# CAN_ESP_control.net
KiCad netlist of a schematic drawn in Altium Designer
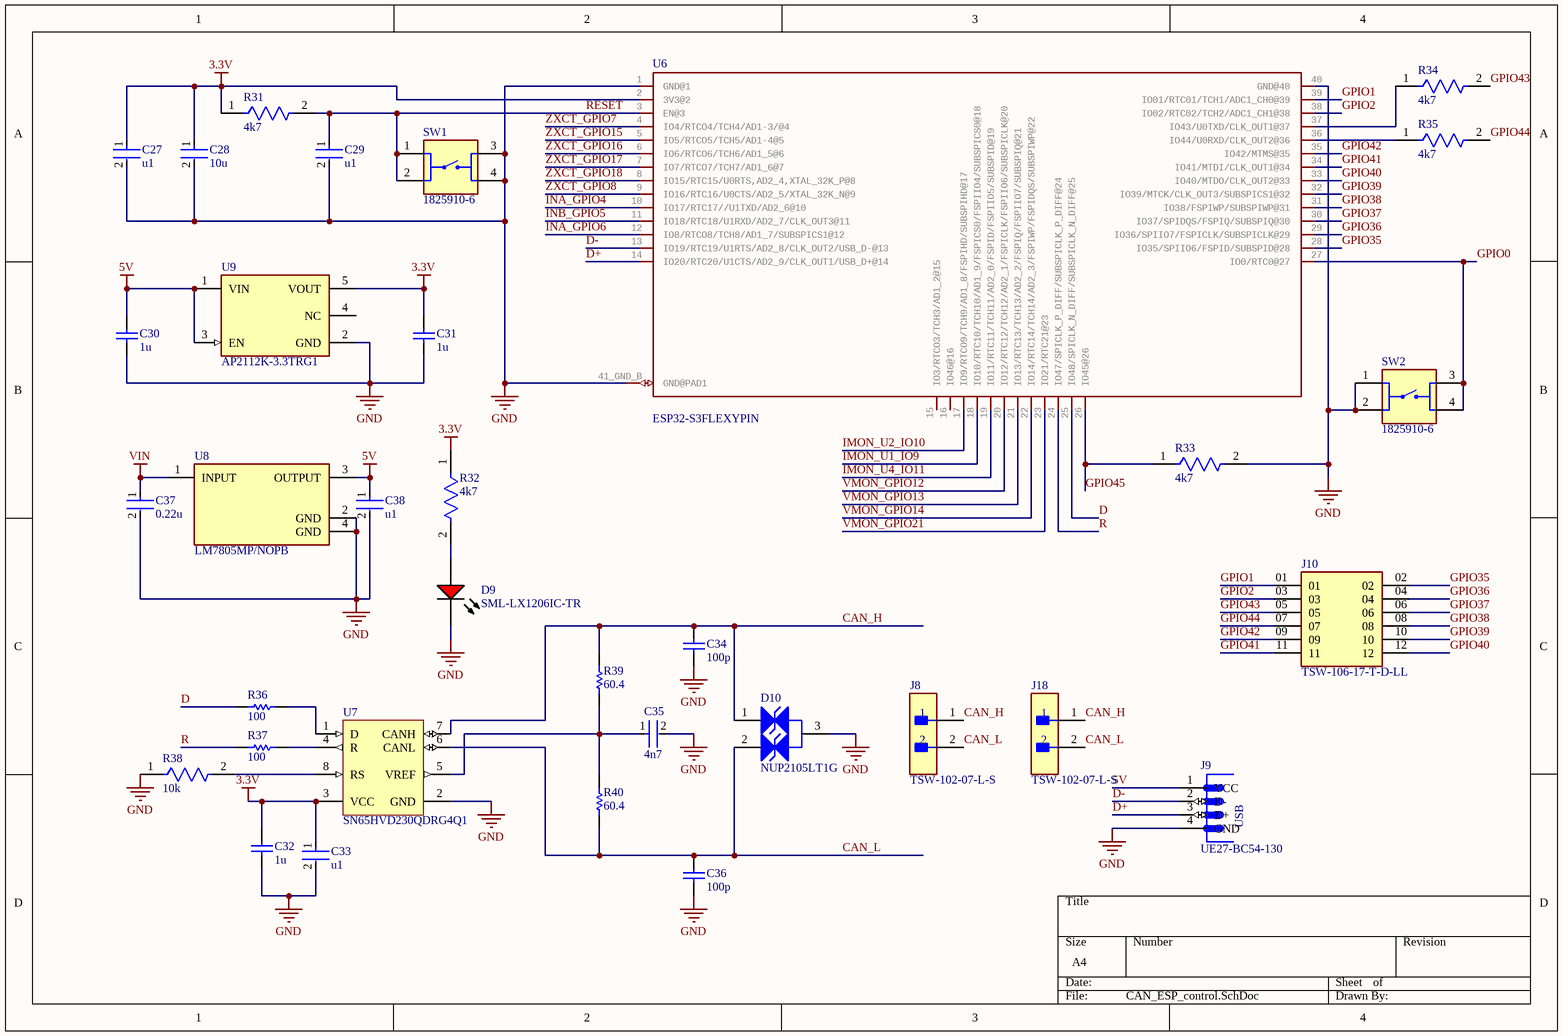
[diagram p0: CAN_ESP_control.SchDoc]

(export (version "E")
  (design (tool "Eeschema 10.0.6"))
  (components
    (comp (ref "C27")
      (value "u1")
      (footprint "FP-CC0805-0_85-MFG")
      (description "CC0805KRX7R9BB104 CAP CER 0.1UF 50V X7R 0805")
      (fields (field (name "TOLERANCE") "0.1") (field (name "MANUFACTURER PART NUMBER") "CC0805KRX7R9BB104"))
      (libsource (lib "Altium Content Vault") (part "11868f565c42a9108669ba33697ecf6"))
    )
    (comp (ref "C28")
      (value "10u")
      (footprint "FP-C0805C-DG-MFG")
      (description "CAP CER 10UF 10V X5R 0805")
      (fields (field (name "TOLERANCE") "10%") (field (name "MANUFACTURER PART NUMBER") "C0805C106K8PACTU"))
      (libsource (lib "Altium Content Vault") (part "11868f565c42a9108669ba33697ecf6"))
    )
    (comp (ref "C29")
      (value "u1")
      (footprint "FP-CC0805-0_85-MFG")
      (description "CC0805KRX7R9BB104 CAP CER 0.1UF 50V X7R 0805")
      (fields (field (name "TOLERANCE") "0.1") (field (name "MANUFACTURER PART NUMBER") "CC0805KRX7R9BB104"))
      (libsource (lib "Altium Content Vault") (part "11868f565c42a9108669ba33697ecf6"))
    )
    (comp (ref "C30")
      (value "1u")
      (footprint "CAPC2013X140X50ML20T25")
      (fields (field (name "MANUFACTURER") "Kemet") (field (name "PART NUMBER") "C0805C105K5RACTU"))
      (libsource (lib "Altium Content Vault") (part "CAP"))
    )
    (comp (ref "C31")
      (value "1u")
      (footprint "CAPC2013X140X50ML20T25")
      (fields (field (name "MANUFACTURER") "Kemet") (field (name "PART NUMBER") "C0805C105K5RACTU"))
      (libsource (lib "Altium Content Vault") (part "CAP"))
    )
    (comp (ref "C32")
      (value "1u")
      (footprint "CAPC2013X140X50ML20T25")
      (fields (field (name "MANUFACTURER") "Kemet") (field (name "PART NUMBER") "C0805C105K5RACTU"))
      (libsource (lib "Altium Content Vault") (part "CAP"))
    )
    (comp (ref "C33")
      (value "u1")
      (footprint "FP-CC0805-0_85-MFG")
      (description "CC0805KRX7R9BB104 CAP CER 0.1UF 50V X7R 0805")
      (fields (field (name "TOLERANCE") "0.1") (field (name "MANUFACTURER PART NUMBER") "CC0805KRX7R9BB104"))
      (libsource (lib "Altium Content Vault") (part "11868f565c42a9108669ba33697ecf6"))
    )
    (comp (ref "C34")
      (value "100p")
      (footprint "CAPC2013X88X50ML20T25")
      (description "C0805C101JCGACTU")
      (fields (field (name "MANUFACTURER") "Kemet"))
      (libsource (lib "Altium Content Vault") (part "CAP"))
    )
    (comp (ref "C35")
      (value "4n7")
      (footprint "FP-0805-L_2_01_0_2-W_1_25-IPC_B")
      (description "08055C472KAT2A General Purpose Ceramic Capacitor, 0805, 4.7nF, 10%, X7R, 0.15, 50V")
      (fields (field (name "VOLTAGE") "50V") (field (name "TOLERANCE") "10%"))
      (libsource (lib "Altium Content Vault") (part "02cd4be3c70576c341d710602a673aa"))
    )
    (comp (ref "C36")
      (value "100p")
      (footprint "CAPC2013X88X50ML20T25")
      (description "C0805C101JCGACTU")
      (fields (field (name "MANUFACTURER") "Kemet"))
      (libsource (lib "Altium Content Vault") (part "CAP"))
    )
    (comp (ref "C37")
      (value "0.22u")
      (footprint "FP-C0805C-DN-MFG")
      (description "CAP CER 0.22UF 50V X7R 0805")
      (fields
        (field (name "MANUFACTURER") "KEMET")
        (field (name "OCTOPART") "https://octopart.com/c0805c224k5ractu-kemet-144670")
      )
      (libsource (lib "Altium Content Vault") (part "b4654b650e69147ec39a6b967a45e02"))
    )
    (comp (ref "C38")
      (value "u1")
      (footprint "FP-CC0805-0_85-MFG")
      (description "CC0805KRX7R9BB104 CAP CER 0.1UF 50V X7R 0805")
      (fields (field (name "TOLERANCE") "0.1") (field (name "MANUFACTURER PART NUMBER") "CC0805KRX7R9BB104"))
      (libsource (lib "Altium Content Vault") (part "11868f565c42a9108669ba33697ecf6"))
    )
    (comp (ref "D9")
      (value "SML-LX1206IC-TR")
      (footprint "LUMX-SML-LX1206IC_V")
      (description "LED Red, 65 mW, -40 to 85 degC, 2-Pin SMD, RoHS, Tape and Reel")
      (fields (field (name "MANUFACTURER") "Lumex"))
      (libsource (lib "Altium Content Vault") (part "LED-RED-AK-2"))
    )
    (comp (ref "D10")
      (value "NUP2105LT1G")
      (footprint "ONSC-SOT-23-3-318-08_V")
      (description "Dual Line CAN Bus Protector, 3-Pin SOT-23, Pb-Free, Tape and Reel")
      (fields (field (name "MANUFACTURER") "On Semiconductor"))
      (libsource (lib "Altium Content Vault") (part "ONSC-NUP21X5X-SOT-23-3-318-08"))
    )
    (comp (ref "J8")
      (value "TSW-102-07-L-S")
      (footprint "FP-TSW-102-07-L-S-MFG")
      (description "CONN HEADER VERT 2POS 2.54MM")
      (libsource (lib "Altium Content Vault") (part "3bc925449376181038e59eaffc5286c"))
    )
    (comp (ref "J9")
      (value "UE27-BC54-130")
      (footprint "AMPHENOL_UE27-BC54-130")
      (description "connector, universal serial bus, type b, rt angle receptacle, black, 4 contact")
      (libsource (lib "PowerDistribution") (part "UE27-BC54-130"))
    )
    (comp (ref "J10")
      (value "TSW-106-17-T-D-LL")
      (footprint "SAMTEC_TSW-106-17-T-D-LL")
      (libsource (lib "PowerDistribution") (part "TSW-106-17-T-D-LL"))
    )
    (comp (ref "J18")
      (value "TSW-102-07-L-S")
      (footprint "FP-TSW-102-07-L-S-MFG")
      (description "CONN HEADER VERT 2POS 2.54MM")
      (libsource (lib "Altium Content Vault") (part "3bc925449376181038e59eaffc5286c"))
    )
    (comp (ref "R31")
      (value "4k7")
      (footprint "FP-CRCW0805-e3-IPC_B")
      (description "CRCW08054K70FKEARES Thick Film, 4.7kΩ, 1%, 0.125W, 100ppm/°C, 0805")
      (fields (field (name "TOLERANCE") "1%"))
      (libsource (lib "Altium Content Vault") (part "1029c3af85768c4190bb7ad29bc67b5"))
    )
    (comp (ref "R32")
      (value "4k7")
      (footprint "FP-CRCW0805-e3-IPC_B")
      (description "CRCW08054K70FKEARES Thick Film, 4.7kΩ, 1%, 0.125W, 100ppm/°C, 0805")
      (fields (field (name "TOLERANCE") "1%"))
      (libsource (lib "Altium Content Vault") (part "1029c3af85768c4190bb7ad29bc67b5"))
    )
    (comp (ref "R33")
      (value "4k7")
      (footprint "FP-CRCW0805-e3-IPC_B")
      (description "CRCW08054K70FKEARES Thick Film, 4.7kΩ, 1%, 0.125W, 100ppm/°C, 0805")
      (fields (field (name "TOLERANCE") "1%"))
      (libsource (lib "Altium Content Vault") (part "1029c3af85768c4190bb7ad29bc67b5"))
    )
    (comp (ref "R34")
      (value "4k7")
      (footprint "FP-CRCW0805-e3-IPC_B")
      (description "CRCW08054K70FKEARES Thick Film, 4.7kΩ, 1%, 0.125W, 100ppm/°C, 0805")
      (fields (field (name "TOLERANCE") "1%"))
      (libsource (lib "Altium Content Vault") (part "1029c3af85768c4190bb7ad29bc67b5"))
    )
    (comp (ref "R35")
      (value "4k7")
      (footprint "FP-CRCW0805-e3-IPC_B")
      (description "CRCW08054K70FKEARES Thick Film, 4.7kΩ, 1%, 0.125W, 100ppm/°C, 0805")
      (fields (field (name "TOLERANCE") "1%"))
      (libsource (lib "Altium Content Vault") (part "1029c3af85768c4190bb7ad29bc67b5"))
    )
    (comp (ref "R36")
      (value "100")
      (footprint "RESC2013X60X35ML10T20")
      (fields (field (name "TOLERANCE") "1%") (field (name "MANUFACTURER") "Yageo"))
      (libsource (lib "Altium Content Vault") (part "RES-2"))
    )
    (comp (ref "R37")
      (value "100")
      (footprint "RESC2013X60X35ML10T20")
      (fields (field (name "TOLERANCE") "1%") (field (name "MANUFACTURER") "Yageo"))
      (libsource (lib "Altium Content Vault") (part "RES-2"))
    )
    (comp (ref "R38")
      (value "10k")
      (footprint "FP-ERA3A-IPC_C")
      (description "RES SMD 10K OHM 0.1% 1/10W 0603")
      (fields (field (name "TOLERANCE") "0.1%"))
      (libsource (lib "Altium Content Vault") (part "4e5f8b3dd332802e91518312df5df73"))
    )
    (comp (ref "R39")
      (value "60.4")
      (footprint "RESC2013X60X35LL10T20")
      (description "RC0805FR-0760R4L")
      (fields (field (name "MANUFACTURER") "Yageo"))
      (libsource (lib "Altium Content Vault") (part "RES"))
    )
    (comp (ref "R40")
      (value "60.4")
      (footprint "RESC2013X60X35LL10T20")
      (description "RC0805FR-0760R4L")
      (fields (field (name "MANUFACTURER") "Yageo"))
      (libsource (lib "Altium Content Vault") (part "RES"))
    )
    (comp (ref "SW1")
      (value "1825910-6")
      (footprint "SW_1825910-6-4")
      (description "Switch Push Button OFF (ON) SPST Round Button 0.05A 24VDC Momentary Contact PC Pins Thru-Hole")
      (fields (field (name "MF") "TE Connectivity") (field (name "DIGI-KEY_PART_NUMBER") "450-1650-ND"))
      (libsource (lib "First") (part "1825910-6"))
    )
    (comp (ref "SW2")
      (value "1825910-6")
      (footprint "SW_1825910-6-4")
      (description "Switch Push Button OFF (ON) SPST Round Button 0.05A 24VDC Momentary Contact PC Pins Thru-Hole")
      (fields (field (name "MF") "TE Connectivity") (field (name "DIGI-KEY_PART_NUMBER") "450-1650-ND"))
      (libsource (lib "First") (part "1825910-6"))
    )
    (comp (ref "U6")
      (value "ESP32-S3FLEXYPIN")
      (footprint "ESP32-S3-FLEXYPIN")
      (libsource (lib "PowerDistribution") (part "ESP32-S3FLEXYPIN"))
    )
    (comp (ref "U7")
      (value "SN65HVD230QDRG4Q1")
      (footprint "D0008A_M")
      (fields (field (name "MANUFACTURER") "Texas Instruments"))
      (libsource (lib "Altium Content Vault") (part "TI-SN65HVD230Q-Q1-SOIC_D-8"))
    )
    (comp (ref "U8")
      (value "LM7805MP/NOPB")
      (footprint "FP-DCY0004A-MFG")
      (description "Linear Voltage Regulator IC 1 Output 1.5A SOT-223-4")
      (fields (field (name "OCTOPART") "https://octopart.com/lm7805mp%2Fnopb-texas+instruments-74629991"))
      (libsource (lib "Altium Content Vault") (part "84c6965c160f0d7e9bd6a72b5b454c6"))
    )
    (comp (ref "U9")
      (value "AP2112K-3.3TRG1")
      (footprint "FP-SOT25-IPC_A")
      (description "IC REG LINEAR 3.3V 600MA SOT25")
      (libsource (lib "Altium Content Vault") (part "c8ab751aee5229183125ab046a11caa"))
    )
  )
  (nets
    (net (code "1") (name "/CAN_H") (class "Default")
      (node (ref "C34") (pin "2") (pinfunction "2_2") (pintype "passive"))
      (node (ref "D10") (pin "1") (pinfunction "K_1") (pintype "passive"))
      (node (ref "J18") (pin "1") (pinfunction "1_1") (pintype "passive"))
      (node (ref "J8") (pin "1") (pinfunction "1_1") (pintype "passive"))
      (node (ref "R39") (pin "2") (pinfunction "2_2") (pintype "passive"))
      (node (ref "U7") (pin "7") (pinfunction "CANH_7") (pintype "bidirectional"))
    )
    (net (code "2") (name "/CAN_L") (class "Default")
      (node (ref "C36") (pin "2") (pinfunction "2_2") (pintype "passive"))
      (node (ref "D10") (pin "2") (pinfunction "K_2") (pintype "passive"))
      (node (ref "J18") (pin "2") (pinfunction "2_2") (pintype "passive"))
      (node (ref "J8") (pin "2") (pinfunction "2_2") (pintype "passive"))
      (node (ref "R40") (pin "1") (pinfunction "1_1") (pintype "passive"))
      (node (ref "U7") (pin "6") (pinfunction "CANL_6") (pintype "bidirectional"))
    )
    (net (code "3") (name "/D") (class "Default")
      (node (ref "R36") (pin "1") (pinfunction "1_1") (pintype "passive"))
      (node (ref "U6") (pin "25") (pinfunction "IO48/SPICLK_N_DIFF/SUBSPICLK_N_DIFF@25_25") (pintype "bidirectional"))
    )
    (net (code "4") (name "/D+") (class "Default")
      (node (ref "J9") (pin "3") (pinfunction "D+_3") (pintype "bidirectional"))
      (node (ref "U6") (pin "14") (pinfunction "IO20/RTC20/U1CTS/AD2_9/CLK_OUT1/USB_D+@14_14") (pintype "bidirectional"))
    )
    (net (code "5") (name "/D-") (class "Default")
      (node (ref "J9") (pin "2") (pinfunction "D-_2") (pintype "bidirectional"))
      (node (ref "U6") (pin "13") (pinfunction "IO19/RTC19/U1RTS/AD2_8/CLK_OUT2/USB_D-@13_13") (pintype "bidirectional"))
    )
    (net (code "6") (name "/GPIO0") (class "Default")
      (node (ref "SW2") (pin "3") (pinfunction "3_3") (pintype "passive"))
      (node (ref "SW2") (pin "4") (pinfunction "4_4") (pintype "passive"))
      (node (ref "U6") (pin "27") (pinfunction "IO0/RTC0@27_27") (pintype "bidirectional"))
    )
    (net (code "7") (name "/GPIO1") (class "Default")
      (node (ref "J10") (pin "01") (pinfunction "01_01") (pintype "passive"))
      (node (ref "U6") (pin "39") (pinfunction "IO01/RTC01/TCH1/ADC1_CH0@39_39") (pintype "bidirectional"))
    )
    (net (code "8") (name "/GPIO2") (class "Default")
      (node (ref "J10") (pin "03") (pinfunction "03_03") (pintype "passive"))
      (node (ref "U6") (pin "38") (pinfunction "IO02/RTC02/TCH2/ADC1_CH1@38_38") (pintype "bidirectional"))
    )
    (net (code "9") (name "/GPIO35") (class "Default")
      (node (ref "J10") (pin "02") (pinfunction "02_02") (pintype "passive"))
      (node (ref "U6") (pin "28") (pinfunction "IO35/SPIIO6/FSPID/SUBSPID@28_28") (pintype "bidirectional"))
    )
    (net (code "10") (name "/GPIO36") (class "Default")
      (node (ref "J10") (pin "04") (pinfunction "04_04") (pintype "passive"))
      (node (ref "U6") (pin "29") (pinfunction "IO36/SPIIO7/FSPICLK/SUBSPICLK@29_29") (pintype "bidirectional"))
    )
    (net (code "11") (name "/GPIO37") (class "Default")
      (node (ref "J10") (pin "06") (pinfunction "06_06") (pintype "passive"))
      (node (ref "U6") (pin "30") (pinfunction "IO37/SPIDQS/FSPIQ/SUBSPIQ@30_30") (pintype "bidirectional"))
    )
    (net (code "12") (name "/GPIO38") (class "Default")
      (node (ref "J10") (pin "08") (pinfunction "08_08") (pintype "passive"))
      (node (ref "U6") (pin "31") (pinfunction "IO38/FSPIWP/SUBSPIWP@31_31") (pintype "bidirectional"))
    )
    (net (code "13") (name "/GPIO39") (class "Default")
      (node (ref "J10") (pin "10") (pinfunction "10_10") (pintype "passive"))
      (node (ref "U6") (pin "32") (pinfunction "IO39/MTCK/CLK_OUT3/SUBSPICS1@32_32") (pintype "bidirectional"))
    )
    (net (code "14") (name "/GPIO40") (class "Default")
      (node (ref "J10") (pin "12") (pinfunction "12_12") (pintype "passive"))
      (node (ref "U6") (pin "33") (pinfunction "IO40/MTDO/CLK_OUT2@33_33") (pintype "bidirectional"))
    )
    (net (code "15") (name "/GPIO41") (class "Default")
      (node (ref "J10") (pin "11") (pinfunction "11_11") (pintype "passive"))
      (node (ref "U6") (pin "34") (pinfunction "IO41/MTDI/CLK_OUT1@34_34") (pintype "bidirectional"))
    )
    (net (code "16") (name "/GPIO42") (class "Default")
      (node (ref "J10") (pin "09") (pinfunction "09_09") (pintype "passive"))
      (node (ref "U6") (pin "35") (pinfunction "IO42/MTMS@35_35") (pintype "bidirectional"))
    )
    (net (code "17") (name "/GPIO43") (class "Default")
      (node (ref "J10") (pin "05") (pinfunction "05_05") (pintype "passive"))
      (node (ref "R34") (pin "2") (pinfunction "2_2") (pintype "passive"))
    )
    (net (code "18") (name "/GPIO44") (class "Default")
      (node (ref "J10") (pin "07") (pinfunction "07_07") (pintype "passive"))
      (node (ref "R35") (pin "2") (pinfunction "2_2") (pintype "passive"))
    )
    (net (code "19") (name "/GPIO45") (class "Default")
      (node (ref "R33") (pin "1") (pinfunction "1_1") (pintype "passive"))
      (node (ref "U6") (pin "26") (pinfunction "IO45@26_26") (pintype "bidirectional"))
    )
    (net (code "20") (name "/IMON_U1_IO9") (class "Default")
      (node (ref "U6") (pin "18") (pinfunction "IO10/RTC10/TCH10/AD1_9/FSPICS0/FSPIIO4/SUBSPICS0@18_18") (pintype "bidirectional"))
    )
    (net (code "21") (name "/IMON_U2_IO10") (class "Default")
      (node (ref "U6") (pin "17") (pinfunction "IO9/RTCO9/TCH9/AD1_8/FSPIHD/SUBSPIHD@17_17") (pintype "bidirectional"))
    )
    (net (code "22") (name "/IMON_U4_IO11") (class "Default")
      (node (ref "U6") (pin "19") (pinfunction "IO11/RTC11/TCH11/AD2_0/FSPID/FSPIIO5/SUBSPID@19_19") (pintype "bidirectional"))
    )
    (net (code "23") (name "/INA_GPIO4") (class "Default")
      (node (ref "U6") (pin "10") (pinfunction "IO17/RTC17//U1TXD/AD2_6@10_10") (pintype "bidirectional"))
    )
    (net (code "24") (name "/INA_GPIO6") (class "Default")
      (node (ref "U6") (pin "12") (pinfunction "IO8/RTCO8/TCH8/AD1_7/SUBSPICS1@12_12") (pintype "bidirectional"))
    )
    (net (code "25") (name "/INB_GPIO5") (class "Default")
      (node (ref "U6") (pin "11") (pinfunction "IO18/RTC18/U1RXD/AD2_7/CLK_OUT3@11_11") (pintype "bidirectional"))
    )
    (net (code "26") (name "/R") (class "Default")
      (node (ref "R37") (pin "1") (pinfunction "1_1") (pintype "passive"))
      (node (ref "U6") (pin "24") (pinfunction "IO47/SPICLK_P_DIFF/SUBSPICLK_P_DIFF@24_24") (pintype "bidirectional"))
    )
    (net (code "27") (name "/RESET") (class "Default")
      (node (ref "C29") (pin "1") (pinfunction "1_1") (pintype "passive"))
      (node (ref "R31") (pin "2") (pinfunction "2_2") (pintype "passive"))
      (node (ref "SW1") (pin "1") (pinfunction "1_1") (pintype "passive"))
      (node (ref "SW1") (pin "2") (pinfunction "2_2") (pintype "passive"))
      (node (ref "U6") (pin "3") (pinfunction "EN@3_3") (pintype "bidirectional"))
    )
    (net (code "28") (name "/VMON_GPIO12") (class "Default")
      (node (ref "U6") (pin "20") (pinfunction "IO12/RTC12/TCH12/AD2_1/FSPICLK/FSPIIO6/SUBSPICLK@20_20") (pintype "bidirectional"))
    )
    (net (code "29") (name "/VMON_GPIO13") (class "Default")
      (node (ref "U6") (pin "21") (pinfunction "IO13/RTC13/TCH13/AD2_2/FSPIQ/FSPIIO7/SUBSPIQ@21_21") (pintype "bidirectional"))
    )
    (net (code "30") (name "/VMON_GPIO14") (class "Default")
      (node (ref "U6") (pin "22") (pinfunction "IO14/RTC14/TCH14/AD2_3/FSPIWP/FSPIDQS/SUBSPIWP@22_22") (pintype "bidirectional"))
    )
    (net (code "31") (name "/VMON_GPIO21") (class "Default")
      (node (ref "U6") (pin "23") (pinfunction "IO21/RTC21@23_23") (pintype "bidirectional"))
    )
    (net (code "32") (name "/ZXCT_GPIO7") (class "Default")
      (node (ref "U6") (pin "4") (pinfunction "IO4/RTCO4/TCH4/AD1-3/@4_4") (pintype "bidirectional"))
    )
    (net (code "33") (name "/ZXCT_GPIO8") (class "Default")
      (node (ref "U6") (pin "9") (pinfunction "IO16/RTC16/U0CTS/AD2_5/XTAL_32K_N@9_9") (pintype "bidirectional"))
    )
    (net (code "34") (name "/ZXCT_GPIO15") (class "Default")
      (node (ref "U6") (pin "5") (pinfunction "IO5/RTCO5/TCH5/AD1-4@5_5") (pintype "bidirectional"))
    )
    (net (code "35") (name "/ZXCT_GPIO16") (class "Default")
      (node (ref "U6") (pin "6") (pinfunction "IO6/RTCO6/TCH6/AD1_5@6_6") (pintype "bidirectional"))
    )
    (net (code "36") (name "/ZXCT_GPIO17") (class "Default")
      (node (ref "U6") (pin "7") (pinfunction "IO7/RTCO7/TCH7/AD1_6@7_7") (pintype "bidirectional"))
    )
    (net (code "37") (name "/ZXCT_GPIO18") (class "Default")
      (node (ref "U6") (pin "8") (pinfunction "IO15/RTC15/U0RTS,AD2_4,XTAL_32K_P@8_8") (pintype "bidirectional"))
    )
    (net (code "38") (name "3.3V") (class "Default")
      (node (ref "C27") (pin "1") (pinfunction "1_1") (pintype "passive"))
      (node (ref "C28") (pin "1") (pinfunction "1_1") (pintype "passive"))
      (node (ref "C31") (pin "2") (pinfunction "2_2") (pintype "passive"))
      (node (ref "C32") (pin "2") (pinfunction "2_2") (pintype "passive"))
      (node (ref "C33") (pin "1") (pinfunction "1_1") (pintype "passive"))
      (node (ref "R31") (pin "1") (pinfunction "1_1") (pintype "passive"))
      (node (ref "R32") (pin "1") (pinfunction "1_1") (pintype "passive"))
      (node (ref "U6") (pin "2") (pinfunction "3V3@2_2") (pintype "bidirectional"))
      (node (ref "U7") (pin "3") (pinfunction "VCC_3") (pintype "power_in"))
      (node (ref "U9") (pin "5") (pinfunction "VOUT_5") (pintype "power_in"))
    )
    (net (code "39") (name "5V") (class "Default")
      (node (ref "C30") (pin "2") (pinfunction "2_2") (pintype "passive"))
      (node (ref "C38") (pin "1") (pinfunction "1_1") (pintype "passive"))
      (node (ref "J9") (pin "1") (pinfunction "VCC_1") (pintype "power_in"))
      (node (ref "U8") (pin "3") (pinfunction "OUTPUT_3") (pintype "power_in"))
      (node (ref "U9") (pin "1") (pinfunction "VIN_1") (pintype "power_in"))
      (node (ref "U9") (pin "3") (pinfunction "EN_3") (pintype "input"))
    )
    (net (code "40") (name "GND") (class "Default")
      (node (ref "C27") (pin "2") (pinfunction "2_2") (pintype "passive"))
      (node (ref "C28") (pin "2") (pinfunction "2_2") (pintype "passive"))
      (node (ref "C29") (pin "2") (pinfunction "2_2") (pintype "passive"))
      (node (ref "C30") (pin "1") (pinfunction "1_1") (pintype "passive"))
      (node (ref "C31") (pin "1") (pinfunction "1_1") (pintype "passive"))
      (node (ref "C32") (pin "1") (pinfunction "1_1") (pintype "passive"))
      (node (ref "C33") (pin "2") (pinfunction "2_2") (pintype "passive"))
      (node (ref "C34") (pin "1") (pinfunction "1_1") (pintype "passive"))
      (node (ref "C35") (pin "2") (pinfunction "2_2") (pintype "passive"))
      (node (ref "C36") (pin "1") (pinfunction "1_1") (pintype "passive"))
      (node (ref "C37") (pin "2") (pinfunction "2_2") (pintype "passive"))
      (node (ref "C38") (pin "2") (pinfunction "2_2") (pintype "passive"))
      (node (ref "D10") (pin "3") (pinfunction "K_3") (pintype "passive"))
      (node (ref "D9") (pin "2") (pinfunction "K_2") (pintype "passive"))
      (node (ref "J9") (pin "4") (pinfunction "GND_4") (pintype "power_in"))
      (node (ref "R33") (pin "2") (pinfunction "2_2") (pintype "passive"))
      (node (ref "R38") (pin "1") (pinfunction "1_1") (pintype "passive"))
      (node (ref "SW1") (pin "3") (pinfunction "3_3") (pintype "passive"))
      (node (ref "SW1") (pin "4") (pinfunction "4_4") (pintype "passive"))
      (node (ref "SW2") (pin "1") (pinfunction "1_1") (pintype "passive"))
      (node (ref "SW2") (pin "2") (pinfunction "2_2") (pintype "passive"))
      (node (ref "U6") (pin "1") (pinfunction "GND@1_1") (pintype "bidirectional"))
      (node (ref "U6") (pin "40") (pinfunction "GND@40_40") (pintype "bidirectional"))
      (node (ref "U6") (pin "41_GND") (pinfunction "GND-PAD1_41_GND") (pintype "bidirectional"))
      (node (ref "U7") (pin "2") (pinfunction "GND_2") (pintype "power_in"))
      (node (ref "U8") (pin "2") (pinfunction "GND_2") (pintype "power_in"))
      (node (ref "U8") (pin "4") (pinfunction "GND_4") (pintype "power_in"))
      (node (ref "U9") (pin "2") (pinfunction "GND_2") (pintype "power_in"))
    )
    (net (code "41") (name "Net-(D9-A)") (class "Default")
      (node (ref "D9") (pin "1") (pinfunction "A_1") (pintype "passive"))
      (node (ref "R32") (pin "2") (pinfunction "2_2") (pintype "passive"))
    )
    (net (code "42") (name "Net-(U6-IO43{slash}U0TXD{slash}CLK_OUT1@37)") (class "Default")
      (node (ref "R34") (pin "1") (pinfunction "1_1") (pintype "passive"))
      (node (ref "U6") (pin "37") (pinfunction "IO43/U0TXD/CLK_OUT1@37_37") (pintype "bidirectional"))
    )
    (net (code "43") (name "Net-(U6-IO44{slash}U0RXD{slash}CLK_OUT2@36)") (class "Default")
      (node (ref "R35") (pin "1") (pinfunction "1_1") (pintype "passive"))
      (node (ref "U6") (pin "36") (pinfunction "IO44/U0RXD/CLK_OUT2@36_36") (pintype "bidirectional"))
    )
    (net (code "44") (name "Net-(U7-D)") (class "Default")
      (node (ref "R36") (pin "2") (pinfunction "2_2") (pintype "passive"))
      (node (ref "U7") (pin "1") (pinfunction "D_1") (pintype "input"))
    )
    (net (code "45") (name "Net-(U7-R)") (class "Default")
      (node (ref "R37") (pin "2") (pinfunction "2_2") (pintype "passive"))
      (node (ref "U7") (pin "4") (pinfunction "R_4") (pintype "output"))
    )
    (net (code "46") (name "Net-(U7-RS)") (class "Default")
      (node (ref "R38") (pin "2") (pinfunction "2_2") (pintype "passive"))
      (node (ref "U7") (pin "8") (pinfunction "RS_8") (pintype "input"))
    )
    (net (code "47") (name "Net-(U7-VREF)") (class "Default")
      (node (ref "C35") (pin "1") (pinfunction "1_1") (pintype "passive"))
      (node (ref "R39") (pin "1") (pinfunction "1_1") (pintype "passive"))
      (node (ref "R40") (pin "2") (pinfunction "2_2") (pintype "passive"))
      (node (ref "U7") (pin "5") (pinfunction "VREF_5") (pintype "output"))
    )
    (net (code "48") (name "VIN") (class "Default")
      (node (ref "C37") (pin "1") (pinfunction "1_1") (pintype "passive"))
      (node (ref "U8") (pin "1") (pinfunction "INPUT_1") (pintype "power_in"))
    )
    (net (code "49") (name "unconnected-(U6-GND@PAD1-Pad41_GND_B)") (class "Default")
      (node (ref "U6") (pin "41_GND_B") (pinfunction "GND@PAD1_41_GND_B") (pintype "bidirectional"))
    )
    (net (code "50") (name "unconnected-(U6-IO3{slash}RTCO3{slash}TCH3{slash}AD1_2@15-Pad15)") (class "Default")
      (node (ref "U6") (pin "15") (pinfunction "IO3/RTCO3/TCH3/AD1_2@15_15") (pintype "bidirectional"))
    )
    (net (code "51") (name "unconnected-(U6-IO46@16-Pad16)") (class "Default")
      (node (ref "U6") (pin "16") (pinfunction "IO46@16_16") (pintype "bidirectional"))
    )
    (net (code "52") (name "unconnected-(U9-NC-Pad4)") (class "Default")
      (node (ref "U9") (pin "4") (pinfunction "NC_4") (pintype "passive"))
    )
  )
)
